# 4-led-smd-v1.net
KiCad netlist of a schematic drawn in EAGLE
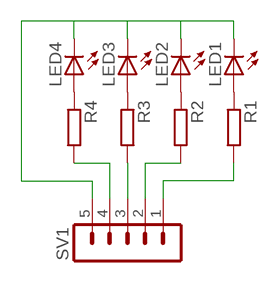
[diagram p0: schematic, sheet 1]

(export (version "E")
  (design (tool "Eeschema 10.0.6"))
  (components
    (comp (ref "LED1")
      (value "LEDCHIP-LED0603")
      (footprint "eagle-import:CHIP-LED0603")
      (libsource (lib "eagle-import") (part "LEDCHIP-LED0603"))
    )
    (comp (ref "LED2")
      (value "LEDCHIP-LED0603")
      (footprint "eagle-import:CHIP-LED0603")
      (libsource (lib "eagle-import") (part "LEDCHIP-LED0603"))
    )
    (comp (ref "LED3")
      (value "LEDCHIP-LED0603")
      (footprint "eagle-import:CHIP-LED0603")
      (libsource (lib "eagle-import") (part "LEDCHIP-LED0603"))
    )
    (comp (ref "LED4")
      (value "LEDCHIP-LED0603")
      (footprint "eagle-import:CHIP-LED0603")
      (libsource (lib "eagle-import") (part "LEDCHIP-LED0603"))
    )
    (comp (ref "R1")
      (value "R-EU_R0603")
      (footprint "eagle-import:R0603")
      (libsource (lib "eagle-import") (part "R-EU_R0603"))
    )
    (comp (ref "R2")
      (value "R-EU_R0603")
      (footprint "eagle-import:R0603")
      (libsource (lib "eagle-import") (part "R-EU_R0603"))
    )
    (comp (ref "R3")
      (value "R-EU_R0603")
      (footprint "eagle-import:R0603")
      (libsource (lib "eagle-import") (part "R-EU_R0603"))
    )
    (comp (ref "R4")
      (value "R-EU_R0603")
      (footprint "eagle-import:R0603")
      (libsource (lib "eagle-import") (part "R-EU_R0603"))
    )
    (comp (ref "SV1")
      (value "MA05-1")
      (footprint "eagle-import:MA05-1")
      (libsource (lib "eagle-import") (part "MA05-1"))
    )
  )
  (nets
    (net (code "1") (name "Net-(LED1-PadA)") (class "Default")
      (node (ref "LED1") (pin "A") (pinfunction "A_A") (pintype "passive"))
      (node (ref "R1") (pin "1") (pinfunction "1_1") (pintype "passive"))
    )
    (net (code "2") (name "Net-(LED1-PadC)") (class "Default")
      (node (ref "LED1") (pin "C") (pinfunction "C_C") (pintype "passive"))
      (node (ref "LED2") (pin "C") (pinfunction "C_C") (pintype "passive"))
      (node (ref "LED3") (pin "C") (pinfunction "C_C") (pintype "passive"))
      (node (ref "LED4") (pin "C") (pinfunction "C_C") (pintype "passive"))
      (node (ref "SV1") (pin "5") (pinfunction "5_5") (pintype "passive"))
    )
    (net (code "3") (name "Net-(LED2-PadA)") (class "Default")
      (node (ref "LED2") (pin "A") (pinfunction "A_A") (pintype "passive"))
      (node (ref "R2") (pin "1") (pinfunction "1_1") (pintype "passive"))
    )
    (net (code "4") (name "Net-(LED3-PadA)") (class "Default")
      (node (ref "LED3") (pin "A") (pinfunction "A_A") (pintype "passive"))
      (node (ref "R3") (pin "1") (pinfunction "1_1") (pintype "passive"))
    )
    (net (code "5") (name "Net-(LED4-PadA)") (class "Default")
      (node (ref "LED4") (pin "A") (pinfunction "A_A") (pintype "passive"))
      (node (ref "R4") (pin "1") (pinfunction "1_1") (pintype "passive"))
    )
    (net (code "6") (name "Net-(R1-Pad2)") (class "Default")
      (node (ref "R1") (pin "2") (pinfunction "2_2") (pintype "passive"))
      (node (ref "SV1") (pin "1") (pinfunction "1_1") (pintype "passive"))
    )
    (net (code "7") (name "Net-(R2-Pad2)") (class "Default")
      (node (ref "R2") (pin "2") (pinfunction "2_2") (pintype "passive"))
      (node (ref "SV1") (pin "2") (pinfunction "2_2") (pintype "passive"))
    )
    (net (code "8") (name "Net-(R3-Pad2)") (class "Default")
      (node (ref "R3") (pin "2") (pinfunction "2_2") (pintype "passive"))
      (node (ref "SV1") (pin "3") (pinfunction "3_3") (pintype "passive"))
    )
    (net (code "9") (name "Net-(R4-Pad2)") (class "Default")
      (node (ref "R4") (pin "2") (pinfunction "2_2") (pintype "passive"))
      (node (ref "SV1") (pin "4") (pinfunction "4_4") (pintype "passive"))
    )
  )
)
